# Therms.net
KiCad netlist of a schematic drawn in Altium Designer
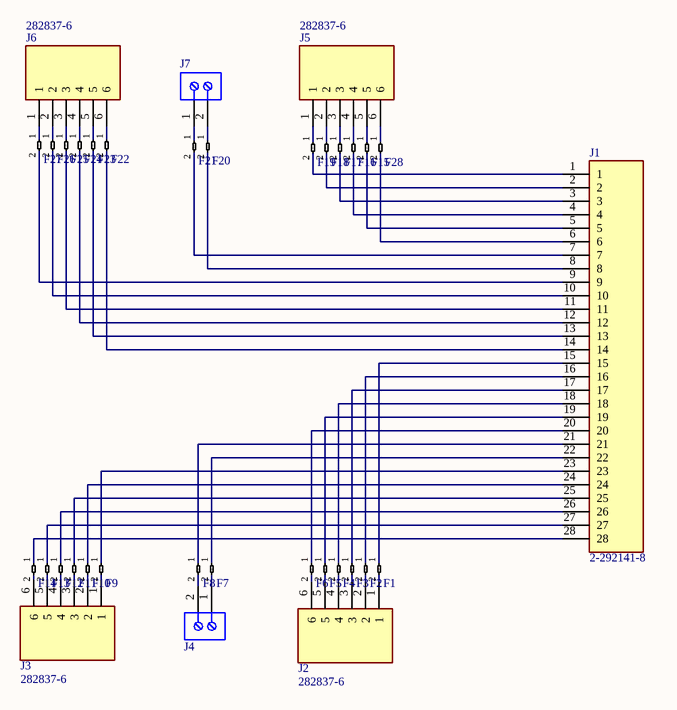
[diagram p0: Therms.SchDoc]

(export (version "E")
  (design (tool "Eeschema 10.0.6"))
  (components
    (comp (ref "F1") (value "C1T5") (footprint "C1T5") (libsource (lib "Bat_Mon-IntgLib") (part "C1T5")))
    (comp (ref "F2") (value "C1T5") (footprint "C1T5") (libsource (lib "Bat_Mon-IntgLib") (part "C1T5")))
    (comp (ref "F3") (value "C1T5") (footprint "C1T5") (libsource (lib "Bat_Mon-IntgLib") (part "C1T5")))
    (comp (ref "F4") (value "C1T5") (footprint "C1T5") (libsource (lib "Bat_Mon-IntgLib") (part "C1T5")))
    (comp (ref "F5") (value "C1T5") (footprint "C1T5") (libsource (lib "Bat_Mon-IntgLib") (part "C1T5")))
    (comp (ref "F6") (value "C1T5") (footprint "C1T5") (libsource (lib "Bat_Mon-IntgLib") (part "C1T5")))
    (comp (ref "F7") (value "C1T5") (footprint "C1T5") (libsource (lib "Bat_Mon-IntgLib") (part "C1T5")))
    (comp (ref "F8") (value "C1T5") (footprint "C1T5") (libsource (lib "Bat_Mon-IntgLib") (part "C1T5")))
    (comp (ref "F9") (value "C1T5") (footprint "C1T5") (libsource (lib "Bat_Mon-IntgLib") (part "C1T5")))
    (comp (ref "F10") (value "C1T5") (footprint "C1T5") (libsource (lib "Bat_Mon-IntgLib") (part "C1T5")))
    (comp (ref "F11") (value "C1T5") (footprint "C1T5") (libsource (lib "Bat_Mon-IntgLib") (part "C1T5")))
    (comp (ref "F12") (value "C1T5") (footprint "C1T5") (libsource (lib "Bat_Mon-IntgLib") (part "C1T5")))
    (comp (ref "F13") (value "C1T5") (footprint "C1T5") (libsource (lib "Bat_Mon-IntgLib") (part "C1T5")))
    (comp (ref "F14") (value "C1T5") (footprint "C1T5") (libsource (lib "Bat_Mon-IntgLib") (part "C1T5")))
    (comp (ref "F15") (value "C1T5") (footprint "C1T5") (libsource (lib "Bat_Mon-IntgLib") (part "C1T5")))
    (comp (ref "F16") (value "C1T5") (footprint "C1T5") (libsource (lib "Bat_Mon-IntgLib") (part "C1T5")))
    (comp (ref "F17") (value "C1T5") (footprint "C1T5") (libsource (lib "Bat_Mon-IntgLib") (part "C1T5")))
    (comp (ref "F18") (value "C1T5") (footprint "C1T5") (libsource (lib "Bat_Mon-IntgLib") (part "C1T5")))
    (comp (ref "F19") (value "C1T5") (footprint "C1T5") (libsource (lib "Bat_Mon-IntgLib") (part "C1T5")))
    (comp (ref "F20") (value "C1T5") (footprint "C1T5") (libsource (lib "Bat_Mon-IntgLib") (part "C1T5")))
    (comp (ref "F21") (value "C1T5") (footprint "C1T5") (libsource (lib "Bat_Mon-IntgLib") (part "C1T5")))
    (comp (ref "F22") (value "C1T5") (footprint "C1T5") (libsource (lib "Bat_Mon-IntgLib") (part "C1T5")))
    (comp (ref "F23") (value "C1T5") (footprint "C1T5") (libsource (lib "Bat_Mon-IntgLib") (part "C1T5")))
    (comp (ref "F24") (value "C1T5") (footprint "C1T5") (libsource (lib "Bat_Mon-IntgLib") (part "C1T5")))
    (comp (ref "F25") (value "C1T5") (footprint "C1T5") (libsource (lib "Bat_Mon-IntgLib") (part "C1T5")))
    (comp (ref "F26") (value "C1T5") (footprint "C1T5") (libsource (lib "Bat_Mon-IntgLib") (part "C1T5")))
    (comp (ref "F27") (value "C1T5") (footprint "C1T5") (libsource (lib "Bat_Mon-IntgLib") (part "C1T5")))
    (comp (ref "F28") (value "C1T5") (footprint "C1T5") (libsource (lib "Bat_Mon-IntgLib") (part "C1T5")))
    (comp (ref "J1")
      (value "2-292141-8")
      (footprint "TE_2-292141-8")
      (fields (field (name "MF") "{'manufacturer': 'TE Connectivity'}"))
      (libsource (lib "2-292141-8") (part "2-292141-8"))
    )
    (comp (ref "J2")
      (value "282837-6")
      (footprint "TE_282837-6")
      (description "Conn Terminal Block F 6 POS 5.08mm Solder ST Thru-Hole 13.5A/Contact")
      (fields (field (name "MF") "TE Connectivity"))
      (libsource (lib "282837-6") (part "282837-6"))
    )
    (comp (ref "J3")
      (value "282837-6")
      (footprint "TE_282837-6")
      (description "Conn Terminal Block F 6 POS 5.08mm Solder ST Thru-Hole 13.5A/Contact")
      (fields (field (name "MF") "TE Connectivity"))
      (libsource (lib "282837-6") (part "282837-6"))
    )
    (comp (ref "J4")
      (value "691102710002")
      (footprint "691102710002")
      (description "Series 102 - 5.00 mm Horizontal Entry Modular with Pressure Clamp WR-TBL, 2 pin")
      (fields (field (name "MANUFACTURER") "Wurth Elektronik") (field (name "PUBLISHER") "WurthElektronik"))
      (libsource (lib "Altium Content Vault") (part "WE-CN-1P-F-TB2"))
    )
    (comp (ref "J5")
      (value "282837-6")
      (footprint "TE_282837-6")
      (description "Conn Terminal Block F 6 POS 5.08mm Solder ST Thru-Hole 13.5A/Contact")
      (fields (field (name "MF") "TE Connectivity"))
      (libsource (lib "") (part "282837-6_1"))
    )
    (comp (ref "J6")
      (value "282837-6")
      (footprint "TE_282837-6")
      (description "Conn Terminal Block F 6 POS 5.08mm Solder ST Thru-Hole 13.5A/Contact")
      (fields (field (name "MF") "TE Connectivity"))
      (libsource (lib "") (part "282837-6_1"))
    )
    (comp (ref "J7")
      (value "691102710002")
      (footprint "691102710002")
      (description "Series 102 - 5.00 mm Horizontal Entry Modular with Pressure Clamp WR-TBL, 2 pin")
      (fields (field (name "MANUFACTURER") "Wurth Elektronik") (field (name "PUBLISHER") "WurthElektronik"))
      (libsource (lib "Altium Content Vault") (part "WE-CN-1P-F-TB2"))
    )
  )
  (nets
    (net (code "1") (name "Net-(F1-Pad1)") (class "Default")
      (node (ref "F1") (pin "1") (pinfunction "1_1") (pintype "passive"))
      (node (ref "J1") (pin "15") (pinfunction "15_15") (pintype "passive"))
    )
    (net (code "2") (name "Net-(F1-Pad2)") (class "Default")
      (node (ref "F1") (pin "2") (pinfunction "2_2") (pintype "passive"))
      (node (ref "J2") (pin "1") (pinfunction "1_1") (pintype "passive"))
    )
    (net (code "3") (name "Net-(F2-Pad1)") (class "Default")
      (node (ref "F2") (pin "1") (pinfunction "1_1") (pintype "passive"))
      (node (ref "J1") (pin "16") (pinfunction "16_16") (pintype "passive"))
    )
    (net (code "4") (name "Net-(F2-Pad2)") (class "Default")
      (node (ref "F2") (pin "2") (pinfunction "2_2") (pintype "passive"))
      (node (ref "J2") (pin "2") (pinfunction "2_2") (pintype "passive"))
    )
    (net (code "5") (name "Net-(F3-Pad1)") (class "Default")
      (node (ref "F3") (pin "1") (pinfunction "1_1") (pintype "passive"))
      (node (ref "J1") (pin "17") (pinfunction "17_17") (pintype "passive"))
    )
    (net (code "6") (name "Net-(F3-Pad2)") (class "Default")
      (node (ref "F3") (pin "2") (pinfunction "2_2") (pintype "passive"))
      (node (ref "J2") (pin "3") (pinfunction "3_3") (pintype "passive"))
    )
    (net (code "7") (name "Net-(F4-Pad1)") (class "Default")
      (node (ref "F4") (pin "1") (pinfunction "1_1") (pintype "passive"))
      (node (ref "J1") (pin "18") (pinfunction "18_18") (pintype "passive"))
    )
    (net (code "8") (name "Net-(F4-Pad2)") (class "Default")
      (node (ref "F4") (pin "2") (pinfunction "2_2") (pintype "passive"))
      (node (ref "J2") (pin "4") (pinfunction "4_4") (pintype "passive"))
    )
    (net (code "9") (name "Net-(F5-Pad1)") (class "Default")
      (node (ref "F5") (pin "1") (pinfunction "1_1") (pintype "passive"))
      (node (ref "J1") (pin "19") (pinfunction "19_19") (pintype "passive"))
    )
    (net (code "10") (name "Net-(F5-Pad2)") (class "Default")
      (node (ref "F5") (pin "2") (pinfunction "2_2") (pintype "passive"))
      (node (ref "J2") (pin "5") (pinfunction "5_5") (pintype "passive"))
    )
    (net (code "11") (name "Net-(F6-Pad1)") (class "Default")
      (node (ref "F6") (pin "1") (pinfunction "1_1") (pintype "passive"))
      (node (ref "J1") (pin "20") (pinfunction "20_20") (pintype "passive"))
    )
    (net (code "12") (name "Net-(F6-Pad2)") (class "Default")
      (node (ref "F6") (pin "2") (pinfunction "2_2") (pintype "passive"))
      (node (ref "J2") (pin "6") (pinfunction "6_6") (pintype "passive"))
    )
    (net (code "13") (name "Net-(F7-Pad1)") (class "Default")
      (node (ref "F7") (pin "1") (pinfunction "1_1") (pintype "passive"))
      (node (ref "J1") (pin "22") (pinfunction "22_22") (pintype "passive"))
    )
    (net (code "14") (name "Net-(F7-Pad2)") (class "Default")
      (node (ref "F7") (pin "2") (pinfunction "2_2") (pintype "passive"))
      (node (ref "J4") (pin "1") (pinfunction "1_1") (pintype "passive"))
    )
    (net (code "15") (name "Net-(F8-Pad1)") (class "Default")
      (node (ref "F8") (pin "1") (pinfunction "1_1") (pintype "passive"))
      (node (ref "J1") (pin "21") (pinfunction "21_21") (pintype "passive"))
    )
    (net (code "16") (name "Net-(F8-Pad2)") (class "Default")
      (node (ref "F8") (pin "2") (pinfunction "2_2") (pintype "passive"))
      (node (ref "J4") (pin "2") (pinfunction "2_2") (pintype "passive"))
    )
    (net (code "17") (name "Net-(F9-Pad1)") (class "Default")
      (node (ref "F9") (pin "1") (pinfunction "1_1") (pintype "passive"))
      (node (ref "J1") (pin "23") (pinfunction "23_23") (pintype "passive"))
    )
    (net (code "18") (name "Net-(F9-Pad2)") (class "Default")
      (node (ref "F9") (pin "2") (pinfunction "2_2") (pintype "passive"))
      (node (ref "J3") (pin "1") (pinfunction "1_1") (pintype "passive"))
    )
    (net (code "19") (name "Net-(F10-Pad1)") (class "Default")
      (node (ref "F10") (pin "1") (pinfunction "1_1") (pintype "passive"))
      (node (ref "J1") (pin "24") (pinfunction "24_24") (pintype "passive"))
    )
    (net (code "20") (name "Net-(F10-Pad2)") (class "Default")
      (node (ref "F10") (pin "2") (pinfunction "2_2") (pintype "passive"))
      (node (ref "J3") (pin "2") (pinfunction "2_2") (pintype "passive"))
    )
    (net (code "21") (name "Net-(F11-Pad1)") (class "Default")
      (node (ref "F11") (pin "1") (pinfunction "1_1") (pintype "passive"))
      (node (ref "J1") (pin "25") (pinfunction "25_25") (pintype "passive"))
    )
    (net (code "22") (name "Net-(F11-Pad2)") (class "Default")
      (node (ref "F11") (pin "2") (pinfunction "2_2") (pintype "passive"))
      (node (ref "J3") (pin "3") (pinfunction "3_3") (pintype "passive"))
    )
    (net (code "23") (name "Net-(F12-Pad1)") (class "Default")
      (node (ref "F12") (pin "1") (pinfunction "1_1") (pintype "passive"))
      (node (ref "J1") (pin "26") (pinfunction "26_26") (pintype "passive"))
    )
    (net (code "24") (name "Net-(F12-Pad2)") (class "Default")
      (node (ref "F12") (pin "2") (pinfunction "2_2") (pintype "passive"))
      (node (ref "J3") (pin "4") (pinfunction "4_4") (pintype "passive"))
    )
    (net (code "25") (name "Net-(F13-Pad1)") (class "Default")
      (node (ref "F13") (pin "1") (pinfunction "1_1") (pintype "passive"))
      (node (ref "J1") (pin "27") (pinfunction "27_27") (pintype "passive"))
    )
    (net (code "26") (name "Net-(F13-Pad2)") (class "Default")
      (node (ref "F13") (pin "2") (pinfunction "2_2") (pintype "passive"))
      (node (ref "J3") (pin "5") (pinfunction "5_5") (pintype "passive"))
    )
    (net (code "27") (name "Net-(F14-Pad1)") (class "Default")
      (node (ref "F14") (pin "1") (pinfunction "1_1") (pintype "passive"))
      (node (ref "J1") (pin "28") (pinfunction "28_28") (pintype "passive"))
    )
    (net (code "28") (name "Net-(F14-Pad2)") (class "Default")
      (node (ref "F14") (pin "2") (pinfunction "2_2") (pintype "passive"))
      (node (ref "J3") (pin "6") (pinfunction "6_6") (pintype "passive"))
    )
    (net (code "29") (name "Net-(F15-Pad1)") (class "Default")
      (node (ref "F15") (pin "1") (pinfunction "1_1") (pintype "passive"))
      (node (ref "J5") (pin "5") (pinfunction "5_5") (pintype "passive"))
    )
    (net (code "30") (name "Net-(F15-Pad2)") (class "Default")
      (node (ref "F15") (pin "2") (pinfunction "2_2") (pintype "passive"))
      (node (ref "J1") (pin "5") (pinfunction "5_5") (pintype "passive"))
    )
    (net (code "31") (name "Net-(F16-Pad1)") (class "Default")
      (node (ref "F16") (pin "1") (pinfunction "1_1") (pintype "passive"))
      (node (ref "J5") (pin "4") (pinfunction "4_4") (pintype "passive"))
    )
    (net (code "32") (name "Net-(F16-Pad2)") (class "Default")
      (node (ref "F16") (pin "2") (pinfunction "2_2") (pintype "passive"))
      (node (ref "J1") (pin "4") (pinfunction "4_4") (pintype "passive"))
    )
    (net (code "33") (name "Net-(F17-Pad1)") (class "Default")
      (node (ref "F17") (pin "1") (pinfunction "1_1") (pintype "passive"))
      (node (ref "J5") (pin "3") (pinfunction "3_3") (pintype "passive"))
    )
    (net (code "34") (name "Net-(F17-Pad2)") (class "Default")
      (node (ref "F17") (pin "2") (pinfunction "2_2") (pintype "passive"))
      (node (ref "J1") (pin "3") (pinfunction "3_3") (pintype "passive"))
    )
    (net (code "35") (name "Net-(F18-Pad1)") (class "Default")
      (node (ref "F18") (pin "1") (pinfunction "1_1") (pintype "passive"))
      (node (ref "J5") (pin "2") (pinfunction "2_2") (pintype "passive"))
    )
    (net (code "36") (name "Net-(F18-Pad2)") (class "Default")
      (node (ref "F18") (pin "2") (pinfunction "2_2") (pintype "passive"))
      (node (ref "J1") (pin "2") (pinfunction "2_2") (pintype "passive"))
    )
    (net (code "37") (name "Net-(F19-Pad1)") (class "Default")
      (node (ref "F19") (pin "1") (pinfunction "1_1") (pintype "passive"))
      (node (ref "J5") (pin "1") (pinfunction "1_1") (pintype "passive"))
    )
    (net (code "38") (name "Net-(F19-Pad2)") (class "Default")
      (node (ref "F19") (pin "2") (pinfunction "2_2") (pintype "passive"))
      (node (ref "J1") (pin "1") (pinfunction "1_1") (pintype "passive"))
    )
    (net (code "39") (name "Net-(F20-Pad1)") (class "Default")
      (node (ref "F20") (pin "1") (pinfunction "1_1") (pintype "passive"))
      (node (ref "J7") (pin "2") (pinfunction "2_2") (pintype "passive"))
    )
    (net (code "40") (name "Net-(F20-Pad2)") (class "Default")
      (node (ref "F20") (pin "2") (pinfunction "2_2") (pintype "passive"))
      (node (ref "J1") (pin "8") (pinfunction "8_8") (pintype "passive"))
    )
    (net (code "41") (name "Net-(F21-Pad1)") (class "Default")
      (node (ref "F21") (pin "1") (pinfunction "1_1") (pintype "passive"))
      (node (ref "J7") (pin "1") (pinfunction "1_1") (pintype "passive"))
    )
    (net (code "42") (name "Net-(F21-Pad2)") (class "Default")
      (node (ref "F21") (pin "2") (pinfunction "2_2") (pintype "passive"))
      (node (ref "J1") (pin "7") (pinfunction "7_7") (pintype "passive"))
    )
    (net (code "43") (name "Net-(F22-Pad1)") (class "Default")
      (node (ref "F22") (pin "1") (pinfunction "1_1") (pintype "passive"))
      (node (ref "J6") (pin "6") (pinfunction "6_6") (pintype "passive"))
    )
    (net (code "44") (name "Net-(F22-Pad2)") (class "Default")
      (node (ref "F22") (pin "2") (pinfunction "2_2") (pintype "passive"))
      (node (ref "J1") (pin "14") (pinfunction "14_14") (pintype "passive"))
    )
    (net (code "45") (name "Net-(F23-Pad1)") (class "Default")
      (node (ref "F23") (pin "1") (pinfunction "1_1") (pintype "passive"))
      (node (ref "J6") (pin "5") (pinfunction "5_5") (pintype "passive"))
    )
    (net (code "46") (name "Net-(F23-Pad2)") (class "Default")
      (node (ref "F23") (pin "2") (pinfunction "2_2") (pintype "passive"))
      (node (ref "J1") (pin "13") (pinfunction "13_13") (pintype "passive"))
    )
    (net (code "47") (name "Net-(F24-Pad1)") (class "Default")
      (node (ref "F24") (pin "1") (pinfunction "1_1") (pintype "passive"))
      (node (ref "J6") (pin "4") (pinfunction "4_4") (pintype "passive"))
    )
    (net (code "48") (name "Net-(F24-Pad2)") (class "Default")
      (node (ref "F24") (pin "2") (pinfunction "2_2") (pintype "passive"))
      (node (ref "J1") (pin "12") (pinfunction "12_12") (pintype "passive"))
    )
    (net (code "49") (name "Net-(F25-Pad1)") (class "Default")
      (node (ref "F25") (pin "1") (pinfunction "1_1") (pintype "passive"))
      (node (ref "J6") (pin "3") (pinfunction "3_3") (pintype "passive"))
    )
    (net (code "50") (name "Net-(F25-Pad2)") (class "Default")
      (node (ref "F25") (pin "2") (pinfunction "2_2") (pintype "passive"))
      (node (ref "J1") (pin "11") (pinfunction "11_11") (pintype "passive"))
    )
    (net (code "51") (name "Net-(F26-Pad1)") (class "Default")
      (node (ref "F26") (pin "1") (pinfunction "1_1") (pintype "passive"))
      (node (ref "J6") (pin "2") (pinfunction "2_2") (pintype "passive"))
    )
    (net (code "52") (name "Net-(F26-Pad2)") (class "Default")
      (node (ref "F26") (pin "2") (pinfunction "2_2") (pintype "passive"))
      (node (ref "J1") (pin "10") (pinfunction "10_10") (pintype "passive"))
    )
    (net (code "53") (name "Net-(F27-Pad1)") (class "Default")
      (node (ref "F27") (pin "1") (pinfunction "1_1") (pintype "passive"))
      (node (ref "J6") (pin "1") (pinfunction "1_1") (pintype "passive"))
    )
    (net (code "54") (name "Net-(F27-Pad2)") (class "Default")
      (node (ref "F27") (pin "2") (pinfunction "2_2") (pintype "passive"))
      (node (ref "J1") (pin "9") (pinfunction "9_9") (pintype "passive"))
    )
    (net (code "55") (name "Net-(F28-Pad1)") (class "Default")
      (node (ref "F28") (pin "1") (pinfunction "1_1") (pintype "passive"))
      (node (ref "J5") (pin "6") (pinfunction "6_6") (pintype "passive"))
    )
    (net (code "56") (name "Net-(F28-Pad2)") (class "Default")
      (node (ref "F28") (pin "2") (pinfunction "2_2") (pintype "passive"))
      (node (ref "J1") (pin "6") (pinfunction "6_6") (pintype "passive"))
    )
  )
)
